# rs485.net
KiCad netlist of a schematic drawn in Altium Designer
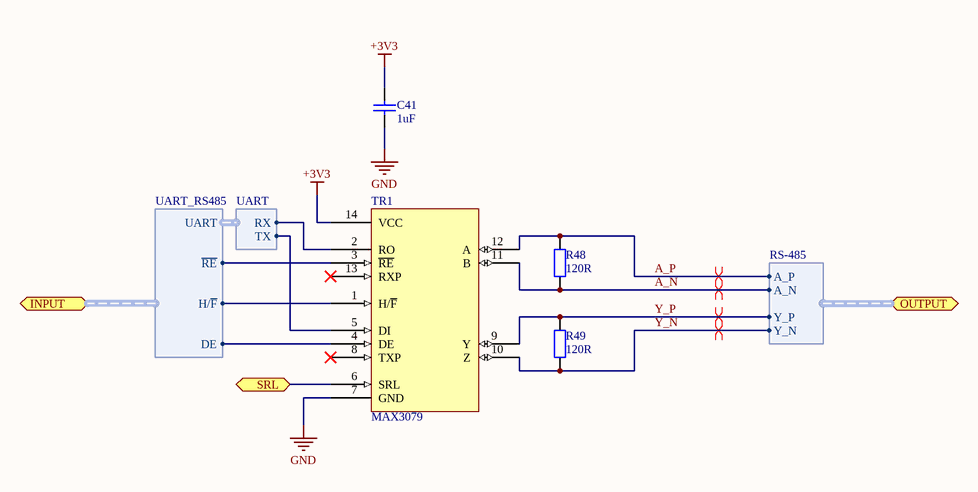
[diagram p0: rs485.SchDoc]

(export (version "E")
  (design (tool "Eeschema 10.0.6"))
  (components
    (comp (ref "C41")
      (value "1uF")
      (footprint "C2012")
      (description "Capacitor")
      (fields
        (field (name "MANUFACTURER") "MULTICOMP")
        (field (name "MANUFACTURER PART NUMBER") "MC0805B105K250CT")
        (field (name "PUBLISHER") "Altium Limited")
      )
      (libsource (lib "Miscellaneous Devices") (part "Cap"))
    )
    (comp (ref "R48")
      (value "120R")
      (footprint "R2012")
      (description "Resistor")
      (fields
        (field (name "MANUFACTURER") "MULTICOMP")
        (field (name "MANUFACTURER PART NUMBER") "MCMR08X1200FTL")
        (field (name "PUBLISHER") "Altium Limited")
      )
      (libsource (lib "") (part "Res2_1"))
    )
    (comp (ref "R49")
      (value "120R")
      (footprint "R2012")
      (description "Resistor")
      (fields
        (field (name "MANUFACTURER") "MULTICOMP")
        (field (name "MANUFACTURER PART NUMBER") "MCMR08X1200FTL")
        (field (name "PUBLISHER") "Altium Limited")
      )
      (libsource (lib "Miscellaneous Devices") (part "Res2"))
    )
    (comp (ref "TR1")
      (value "MAX3079")
      (footprint "SOIC14")
      (description "MAX3079 RS485-Transreceiver")
      (libsource (lib "bitbots") (part "MAX3079"))
    )
  )
  (nets
    (net (code "4") (name "+3V3") (class "Default")
      (node (ref "C41") (pin "1") (pinfunction "1_1") (pintype "passive"))
      (node (ref "TR1") (pin "14") (pinfunction "VCC_14") (pintype "power_in"))
    )
    (net (code "5") (name "/A_N") (class "Default")
      (node (ref "R48") (pin "1") (pinfunction "1_1") (pintype "passive"))
      (node (ref "TR1") (pin "11") (pinfunction "B_11") (pintype "bidirectional"))
    )
    (net (code "6") (name "/A_P") (class "Default")
      (node (ref "R48") (pin "2") (pinfunction "2_2") (pintype "passive"))
      (node (ref "TR1") (pin "12") (pinfunction "A_12") (pintype "bidirectional"))
    )
    (net (code "7") (name "/DE") (class "Default")
      (node (ref "TR1") (pin "4") (pinfunction "DE_4") (pintype "input"))
    )
    (net (code "8") (name "/H{slash}~{F}") (class "Default")
      (node (ref "TR1") (pin "1") (pinfunction "H/~{F}_1") (pintype "input"))
    )
    (net (code "10") (name "/RX") (class "Default")
      (node (ref "TR1") (pin "2") (pinfunction "RO_2") (pintype "passive"))
    )
    (net (code "11") (name "/SRL") (class "Default")
      (node (ref "TR1") (pin "6") (pinfunction "SRL_6") (pintype "input"))
    )
    (net (code "12") (name "/TX") (class "Default")
      (node (ref "TR1") (pin "5") (pinfunction "DI_5") (pintype "input"))
    )
    (net (code "13") (name "/Y_N") (class "Default")
      (node (ref "R49") (pin "2") (pinfunction "2_2") (pintype "passive"))
      (node (ref "TR1") (pin "10") (pinfunction "Z_10") (pintype "bidirectional"))
    )
    (net (code "14") (name "/Y_P") (class "Default")
      (node (ref "R49") (pin "1") (pinfunction "1_1") (pintype "passive"))
      (node (ref "TR1") (pin "9") (pinfunction "Y_9") (pintype "bidirectional"))
    )
    (net (code "17") (name "/~{RE}") (class "Default")
      (node (ref "TR1") (pin "3") (pinfunction "~{RE}_3") (pintype "input"))
    )
    (net (code "18") (name "GND") (class "Default")
      (node (ref "C41") (pin "2") (pinfunction "2_2") (pintype "passive"))
      (node (ref "TR1") (pin "7") (pinfunction "GND_7") (pintype "power_in"))
    )
    (net (code "19") (name "unconnected-(TR1-RXP-Pad13)") (class "Default")
      (node (ref "TR1") (pin "13") (pinfunction "RXP_13") (pintype "input+no_connect"))
    )
    (net (code "20") (name "unconnected-(TR1-TXP-Pad8)") (class "Default")
      (node (ref "TR1") (pin "8") (pinfunction "TXP_8") (pintype "input+no_connect"))
    )
  )
)
